# lcd_buckler_mk_2.net
KiCad netlist of a schematic drawn in EAGLE
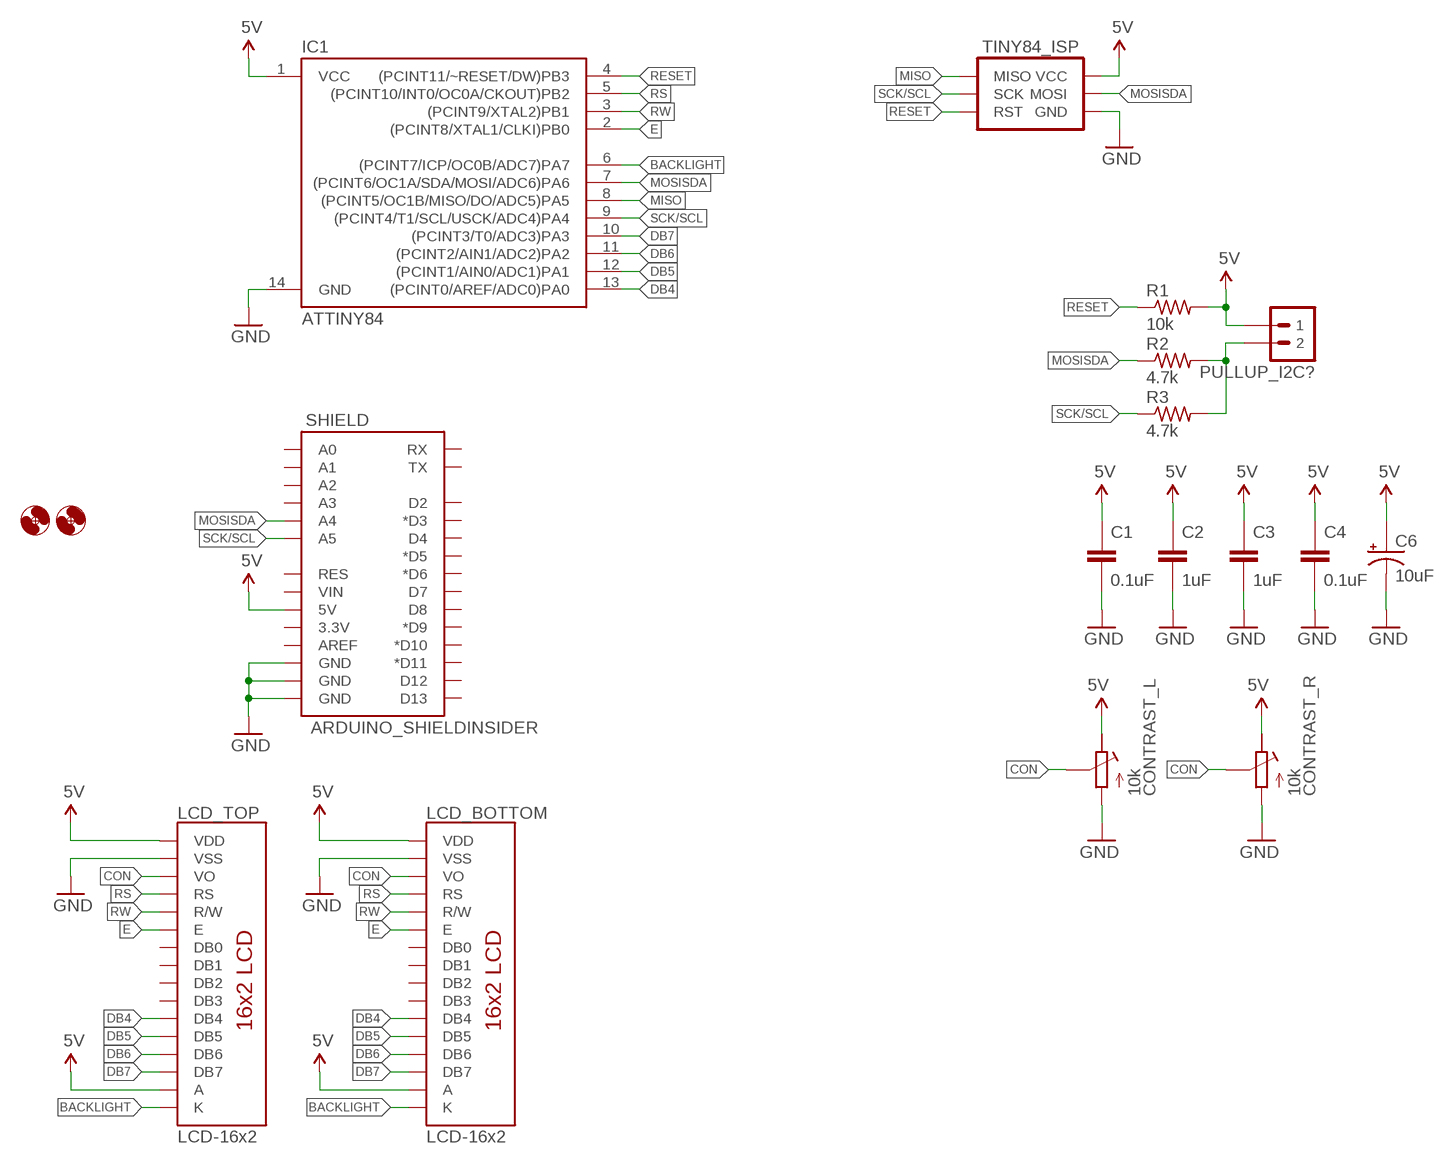
[diagram p0: schematic, sheet 1]

(export (version "E")
  (design (tool "Eeschema 10.0.6"))
  (components
    (comp (ref "C1")
      (value "0.1uF")
      (footprint "eagle-import:C0805")
      (libsource (lib "eagle-import") (part "CAPACITOR-CERAMICC0805"))
    )
    (comp (ref "C2")
      (value "1uF")
      (footprint "eagle-import:C025-024X044")
      (libsource (lib "eagle-import") (part "CAPACITOR-CERAMIC025-024X044"))
    )
    (comp (ref "C3")
      (value "1uF")
      (footprint "eagle-import:C025-024X044")
      (libsource (lib "eagle-import") (part "CAPACITOR-CERAMIC025-024X044"))
    )
    (comp (ref "C4")
      (value "0.1uF")
      (footprint "eagle-import:C025-024X044")
      (libsource (lib "eagle-import") (part "CAPACITOR-CERAMIC025-024X044"))
    )
    (comp (ref "C6")
      (value "10uF")
      (footprint "eagle-import:E2,5-5")
      (libsource (lib "eagle-import") (part "CAPACITOR-POLARIZEDE2.5-5"))
    )
    (comp (ref "CONTRAST_L")
      (value "10k")
      (footprint "eagle-import:POT-THUMBWHEEL")
      (libsource (lib "eagle-import") (part "POTENTIOMETERTHUMBWHEEL-16MM"))
    )
    (comp (ref "CONTRAST_R")
      (value "10k")
      (footprint "eagle-import:POT-THUMBWHEEL")
      (libsource (lib "eagle-import") (part "POTENTIOMETERTHUMBWHEEL-16MM"))
    )
    (comp (ref "H1")
      (value "HOLE#2")
      (footprint "eagle-import:HOLE-#2")
      (libsource (lib "eagle-import") (part "HOLE#2"))
    )
    (comp (ref "H2")
      (value "HOLE#2")
      (footprint "eagle-import:HOLE-#2")
      (libsource (lib "eagle-import") (part "HOLE#2"))
    )
    (comp (ref "IC1")
      (value "ATTINY84")
      (footprint "eagle-import:SO14")
      (libsource (lib "eagle-import") (part "ATTINY84"))
    )
    (comp (ref "LCD_BOTTOM")
      (value "LCD-16x2")
      (footprint "eagle-import:LCD-16X2-PINS-ONLY")
      (libsource (lib "eagle-import") (part "LCD-16X2HOLESONLY"))
    )
    (comp (ref "LCD_TOP")
      (value "LCD-16x2")
      (footprint "eagle-import:LCD-16X2-PINS-ONLY")
      (libsource (lib "eagle-import") (part "LCD-16X2HOLESONLY"))
    )
    (comp (ref "PULLUP_I2C?")
      (value "M02PTH")
      (footprint "eagle-import:1X02")
      (libsource (lib "eagle-import") (part "M02PTH"))
    )
    (comp (ref "R1")
      (value "10k")
      (footprint "eagle-import:R0805")
      (libsource (lib "eagle-import") (part "RESISTORR0805"))
    )
    (comp (ref "R2")
      (value "4.7k")
      (footprint "eagle-import:RESISTOR-AXIAL-PTH-7.68MM")
      (libsource (lib "eagle-import") (part "RESISTORPTH-AXIAL-7.68MM"))
    )
    (comp (ref "R3")
      (value "4.7k")
      (footprint "eagle-import:RESISTOR-AXIAL-PTH-7.68MM")
      (libsource (lib "eagle-import") (part "RESISTORPTH-AXIAL-7.68MM"))
    )
    (comp (ref "SHIELD")
      (value "ARDUINO_SHIELDINSIDER")
      (footprint "eagle-import:ARDUINO_SHIELD_NOOUTLINE_INSIDE")
      (libsource (lib "eagle-import") (part "ARDUINO_SHIELDINSIDER"))
    )
    (comp (ref "TINY84_ISP")
      (value "AVR_SPI_PRG_6PTH")
      (footprint "eagle-import:2X3")
      (libsource (lib "eagle-import") (part "AVR_SPI_PRG_6PTH"))
    )
  )
  (nets
    (net (code "1") (name "5V") (class "Default")
      (node (ref "C1") (pin "1") (pinfunction "1_1") (pintype "passive"))
      (node (ref "C2") (pin "1") (pinfunction "1_1") (pintype "passive"))
      (node (ref "C3") (pin "1") (pinfunction "1_1") (pintype "passive"))
      (node (ref "C4") (pin "1") (pinfunction "1_1") (pintype "passive"))
      (node (ref "C6") (pin "+") (pinfunction "+_+") (pintype "passive"))
      (node (ref "CONTRAST_L") (pin "3") (pinfunction "E_3") (pintype "passive"))
      (node (ref "CONTRAST_R") (pin "3") (pinfunction "E_3") (pintype "passive"))
      (node (ref "IC1") (pin "1") (pinfunction "VCC_1") (pintype "bidirectional"))
      (node (ref "LCD_BOTTOM") (pin "15") (pinfunction "A_15") (pintype "power_in"))
      (node (ref "LCD_BOTTOM") (pin "2") (pinfunction "VDD_2") (pintype "power_in"))
      (node (ref "LCD_TOP") (pin "15") (pinfunction "A_15") (pintype "power_in"))
      (node (ref "LCD_TOP") (pin "2") (pinfunction "VDD_2") (pintype "power_in"))
      (node (ref "PULLUP_I2C?") (pin "1") (pinfunction "1_1") (pintype "passive"))
      (node (ref "R1") (pin "2") (pinfunction "2_2") (pintype "passive"))
      (node (ref "SHIELD") (pin "5V") (pinfunction "5V_5V") (pintype "bidirectional"))
      (node (ref "TINY84_ISP") (pin "2") (pinfunction "VCC_2") (pintype "passive"))
    )
    (net (code "2") (name "BACKLIGHT") (class "Default")
      (node (ref "IC1") (pin "6") (pinfunction "(PCINT7/ICP/OC0B/ADC7)PA7_6") (pintype "bidirectional"))
      (node (ref "LCD_BOTTOM") (pin "16") (pinfunction "K_16") (pintype "power_in"))
      (node (ref "LCD_TOP") (pin "16") (pinfunction "K_16") (pintype "power_in"))
    )
    (net (code "3") (name "CON") (class "Default")
      (node (ref "CONTRAST_L") (pin "2") (pinfunction "S_2") (pintype "passive"))
      (node (ref "CONTRAST_L") (pin "2@1") (pinfunction "S_2@1") (pintype "passive"))
      (node (ref "CONTRAST_R") (pin "2") (pinfunction "S_2") (pintype "passive"))
      (node (ref "CONTRAST_R") (pin "2@1") (pinfunction "S_2@1") (pintype "passive"))
      (node (ref "LCD_BOTTOM") (pin "3") (pinfunction "VO_3") (pintype "bidirectional"))
      (node (ref "LCD_TOP") (pin "3") (pinfunction "VO_3") (pintype "bidirectional"))
    )
    (net (code "4") (name "DB4") (class "Default")
      (node (ref "IC1") (pin "13") (pinfunction "(PCINT0/AREF/ADC0)PA0_13") (pintype "bidirectional"))
      (node (ref "LCD_BOTTOM") (pin "11") (pinfunction "DB4_11") (pintype "bidirectional"))
      (node (ref "LCD_TOP") (pin "11") (pinfunction "DB4_11") (pintype "bidirectional"))
    )
    (net (code "5") (name "DB5") (class "Default")
      (node (ref "IC1") (pin "12") (pinfunction "(PCINT1/AIN0/ADC1)PA1_12") (pintype "bidirectional"))
      (node (ref "LCD_BOTTOM") (pin "12") (pinfunction "DB5_12") (pintype "bidirectional"))
      (node (ref "LCD_TOP") (pin "12") (pinfunction "DB5_12") (pintype "bidirectional"))
    )
    (net (code "6") (name "DB6") (class "Default")
      (node (ref "IC1") (pin "11") (pinfunction "(PCINT2/AIN1/ADC2)PA2_11") (pintype "bidirectional"))
      (node (ref "LCD_BOTTOM") (pin "13") (pinfunction "DB6_13") (pintype "bidirectional"))
      (node (ref "LCD_TOP") (pin "13") (pinfunction "DB6_13") (pintype "bidirectional"))
    )
    (net (code "7") (name "DB7") (class "Default")
      (node (ref "IC1") (pin "10") (pinfunction "(PCINT3/T0/ADC3)PA3_10") (pintype "bidirectional"))
      (node (ref "LCD_BOTTOM") (pin "14") (pinfunction "DB7_14") (pintype "bidirectional"))
      (node (ref "LCD_TOP") (pin "14") (pinfunction "DB7_14") (pintype "bidirectional"))
    )
    (net (code "8") (name "E") (class "Default")
      (node (ref "IC1") (pin "2") (pinfunction "(PCINT8/XTAL1/CLKI)PB0_2") (pintype "bidirectional"))
      (node (ref "LCD_BOTTOM") (pin "6") (pinfunction "E_6") (pintype "input"))
      (node (ref "LCD_TOP") (pin "6") (pinfunction "E_6") (pintype "input"))
    )
    (net (code "9") (name "GND") (class "Default")
      (node (ref "C1") (pin "2") (pinfunction "2_2") (pintype "passive"))
      (node (ref "C2") (pin "2") (pinfunction "2_2") (pintype "passive"))
      (node (ref "C3") (pin "2") (pinfunction "2_2") (pintype "passive"))
      (node (ref "C4") (pin "2") (pinfunction "2_2") (pintype "passive"))
      (node (ref "C6") (pin "-") (pinfunction "-_-") (pintype "passive"))
      (node (ref "CONTRAST_L") (pin "1") (pinfunction "A_1") (pintype "passive"))
      (node (ref "CONTRAST_R") (pin "1") (pinfunction "A_1") (pintype "passive"))
      (node (ref "IC1") (pin "14") (pinfunction "GND_14") (pintype "bidirectional"))
      (node (ref "LCD_BOTTOM") (pin "1") (pinfunction "VSS_1") (pintype "power_in"))
      (node (ref "LCD_TOP") (pin "1") (pinfunction "VSS_1") (pintype "power_in"))
      (node (ref "SHIELD") (pin "GND@0") (pinfunction "GND_GND@0") (pintype "bidirectional"))
      (node (ref "SHIELD") (pin "GND@1") (pinfunction "GND_GND@1") (pintype "bidirectional"))
      (node (ref "SHIELD") (pin "GND@2") (pinfunction "GND_GND@2") (pintype "bidirectional"))
      (node (ref "TINY84_ISP") (pin "6") (pinfunction "GND_6") (pintype "passive"))
    )
    (net (code "10") (name "MISO") (class "Default")
      (node (ref "IC1") (pin "8") (pinfunction "(PCINT5/OC1B/MISO/DO/ADC5)PA5_8") (pintype "bidirectional"))
      (node (ref "TINY84_ISP") (pin "1") (pinfunction "MISO_1") (pintype "passive"))
    )
    (net (code "11") (name "MOSISDA") (class "Default")
      (node (ref "IC1") (pin "7") (pinfunction "(PCINT6/OC1A/SDA/MOSI/ADC6)PA6_7") (pintype "bidirectional"))
      (node (ref "R2") (pin "P$1") (pinfunction "1_P$1") (pintype "passive"))
      (node (ref "SHIELD") (pin "A4") (pinfunction "A4_A4") (pintype "bidirectional"))
      (node (ref "TINY84_ISP") (pin "4") (pinfunction "MOSI_4") (pintype "passive"))
    )
    (net (code "12") (name "Net-(R2-2)") (class "Default")
      (node (ref "PULLUP_I2C?") (pin "2") (pinfunction "2_2") (pintype "passive"))
      (node (ref "R2") (pin "P$2") (pinfunction "2_P$2") (pintype "passive"))
      (node (ref "R3") (pin "P$2") (pinfunction "2_P$2") (pintype "passive"))
    )
    (net (code "13") (name "RESET") (class "Default")
      (node (ref "IC1") (pin "4") (pinfunction "(PCINT11/~{RESET/DW})PB3_4") (pintype "bidirectional"))
      (node (ref "R1") (pin "1") (pinfunction "1_1") (pintype "passive"))
      (node (ref "TINY84_ISP") (pin "5") (pinfunction "RST_5") (pintype "passive"))
    )
    (net (code "14") (name "RS") (class "Default")
      (node (ref "IC1") (pin "5") (pinfunction "(PCINT10/INT0/OC0A/CKOUT)PB2_5") (pintype "bidirectional"))
      (node (ref "LCD_BOTTOM") (pin "4") (pinfunction "RS_4") (pintype "input"))
      (node (ref "LCD_TOP") (pin "4") (pinfunction "RS_4") (pintype "input"))
    )
    (net (code "15") (name "RW") (class "Default")
      (node (ref "IC1") (pin "3") (pinfunction "(PCINT9/XTAL2)PB1_3") (pintype "bidirectional"))
      (node (ref "LCD_BOTTOM") (pin "5") (pinfunction "R/W_5") (pintype "input"))
      (node (ref "LCD_TOP") (pin "5") (pinfunction "R/W_5") (pintype "input"))
    )
    (net (code "16") (name "SCK{slash}SCL") (class "Default")
      (node (ref "IC1") (pin "9") (pinfunction "(PCINT4/T1/SCL/USCK/ADC4)PA4_9") (pintype "bidirectional"))
      (node (ref "R3") (pin "P$1") (pinfunction "1_P$1") (pintype "passive"))
      (node (ref "SHIELD") (pin "A5") (pinfunction "A5_A5") (pintype "bidirectional"))
      (node (ref "TINY84_ISP") (pin "3") (pinfunction "SCK_3") (pintype "passive"))
    )
    (net (code "17") (name "unconnected-(LCD_BOTTOM-DB0-Pad7)") (class "Default")
      (node (ref "LCD_BOTTOM") (pin "7") (pinfunction "DB0_7") (pintype "bidirectional"))
    )
    (net (code "18") (name "unconnected-(LCD_BOTTOM-DB1-Pad8)") (class "Default")
      (node (ref "LCD_BOTTOM") (pin "8") (pinfunction "DB1_8") (pintype "bidirectional"))
    )
    (net (code "19") (name "unconnected-(LCD_BOTTOM-DB2-Pad9)") (class "Default")
      (node (ref "LCD_BOTTOM") (pin "9") (pinfunction "DB2_9") (pintype "bidirectional"))
    )
    (net (code "20") (name "unconnected-(LCD_BOTTOM-DB3-Pad10)") (class "Default")
      (node (ref "LCD_BOTTOM") (pin "10") (pinfunction "DB3_10") (pintype "bidirectional"))
    )
    (net (code "21") (name "unconnected-(LCD_TOP-DB0-Pad7)") (class "Default")
      (node (ref "LCD_TOP") (pin "7") (pinfunction "DB0_7") (pintype "bidirectional"))
    )
    (net (code "22") (name "unconnected-(LCD_TOP-DB1-Pad8)") (class "Default")
      (node (ref "LCD_TOP") (pin "8") (pinfunction "DB1_8") (pintype "bidirectional"))
    )
    (net (code "23") (name "unconnected-(LCD_TOP-DB2-Pad9)") (class "Default")
      (node (ref "LCD_TOP") (pin "9") (pinfunction "DB2_9") (pintype "bidirectional"))
    )
    (net (code "24") (name "unconnected-(LCD_TOP-DB3-Pad10)") (class "Default")
      (node (ref "LCD_TOP") (pin "10") (pinfunction "DB3_10") (pintype "bidirectional"))
    )
    (net (code "25") (name "unconnected-(SHIELD-*D3-PadD3)") (class "Default")
      (node (ref "SHIELD") (pin "D3") (pinfunction "*D3_D3") (pintype "bidirectional"))
    )
    (net (code "26") (name "unconnected-(SHIELD-*D5-PadD5)") (class "Default")
      (node (ref "SHIELD") (pin "D5") (pinfunction "*D5_D5") (pintype "bidirectional"))
    )
    (net (code "27") (name "unconnected-(SHIELD-*D6-PadD6)") (class "Default")
      (node (ref "SHIELD") (pin "D6") (pinfunction "*D6_D6") (pintype "bidirectional"))
    )
    (net (code "28") (name "unconnected-(SHIELD-*D9-PadD9)") (class "Default")
      (node (ref "SHIELD") (pin "D9") (pinfunction "*D9_D9") (pintype "bidirectional"))
    )
    (net (code "29") (name "unconnected-(SHIELD-*D10-PadD10)") (class "Default")
      (node (ref "SHIELD") (pin "D10") (pinfunction "*D10_D10") (pintype "bidirectional"))
    )
    (net (code "30") (name "unconnected-(SHIELD-*D11-PadD11)") (class "Default")
      (node (ref "SHIELD") (pin "D11") (pinfunction "*D11_D11") (pintype "bidirectional"))
    )
    (net (code "31") (name "unconnected-(SHIELD-Pad3.3V)") (class "Default")
      (node (ref "SHIELD") (pin "3.3V") (pinfunction "3.3V_3.3V") (pintype "bidirectional"))
    )
    (net (code "32") (name "unconnected-(SHIELD-PadA0)") (class "Default")
      (node (ref "SHIELD") (pin "A0") (pinfunction "A0_A0") (pintype "bidirectional"))
    )
    (net (code "33") (name "unconnected-(SHIELD-PadA1)") (class "Default")
      (node (ref "SHIELD") (pin "A1") (pinfunction "A1_A1") (pintype "bidirectional"))
    )
    (net (code "34") (name "unconnected-(SHIELD-PadA2)") (class "Default")
      (node (ref "SHIELD") (pin "A2") (pinfunction "A2_A2") (pintype "bidirectional"))
    )
    (net (code "35") (name "unconnected-(SHIELD-PadA3)") (class "Default")
      (node (ref "SHIELD") (pin "A3") (pinfunction "A3_A3") (pintype "bidirectional"))
    )
    (net (code "36") (name "unconnected-(SHIELD-PadAREF)") (class "Default")
      (node (ref "SHIELD") (pin "AREF") (pinfunction "AREF_AREF") (pintype "bidirectional"))
    )
    (net (code "37") (name "unconnected-(SHIELD-PadD2)") (class "Default")
      (node (ref "SHIELD") (pin "D2") (pinfunction "D2_D2") (pintype "bidirectional"))
    )
    (net (code "38") (name "unconnected-(SHIELD-PadD4)") (class "Default")
      (node (ref "SHIELD") (pin "D4") (pinfunction "D4_D4") (pintype "bidirectional"))
    )
    (net (code "39") (name "unconnected-(SHIELD-PadD7)") (class "Default")
      (node (ref "SHIELD") (pin "D7") (pinfunction "D7_D7") (pintype "bidirectional"))
    )
    (net (code "40") (name "unconnected-(SHIELD-PadD8)") (class "Default")
      (node (ref "SHIELD") (pin "D8") (pinfunction "D8_D8") (pintype "bidirectional"))
    )
    (net (code "41") (name "unconnected-(SHIELD-PadD12)") (class "Default")
      (node (ref "SHIELD") (pin "D12") (pinfunction "D12_D12") (pintype "bidirectional"))
    )
    (net (code "42") (name "unconnected-(SHIELD-PadD13)") (class "Default")
      (node (ref "SHIELD") (pin "D13") (pinfunction "D13_D13") (pintype "bidirectional"))
    )
    (net (code "43") (name "unconnected-(SHIELD-PadRES)") (class "Default")
      (node (ref "SHIELD") (pin "RES") (pinfunction "RES_RES") (pintype "bidirectional"))
    )
    (net (code "44") (name "unconnected-(SHIELD-PadRX)") (class "Default")
      (node (ref "SHIELD") (pin "RX") (pinfunction "RX_RX") (pintype "bidirectional"))
    )
    (net (code "45") (name "unconnected-(SHIELD-PadTX)") (class "Default")
      (node (ref "SHIELD") (pin "TX") (pinfunction "TX_TX") (pintype "bidirectional"))
    )
    (net (code "46") (name "unconnected-(SHIELD-PadVIN)") (class "Default")
      (node (ref "SHIELD") (pin "VIN") (pinfunction "VIN_VIN") (pintype "bidirectional"))
    )
  )
)
